# DMX_Eval_Board.net
KiCad netlist of a schematic drawn in EAGLE
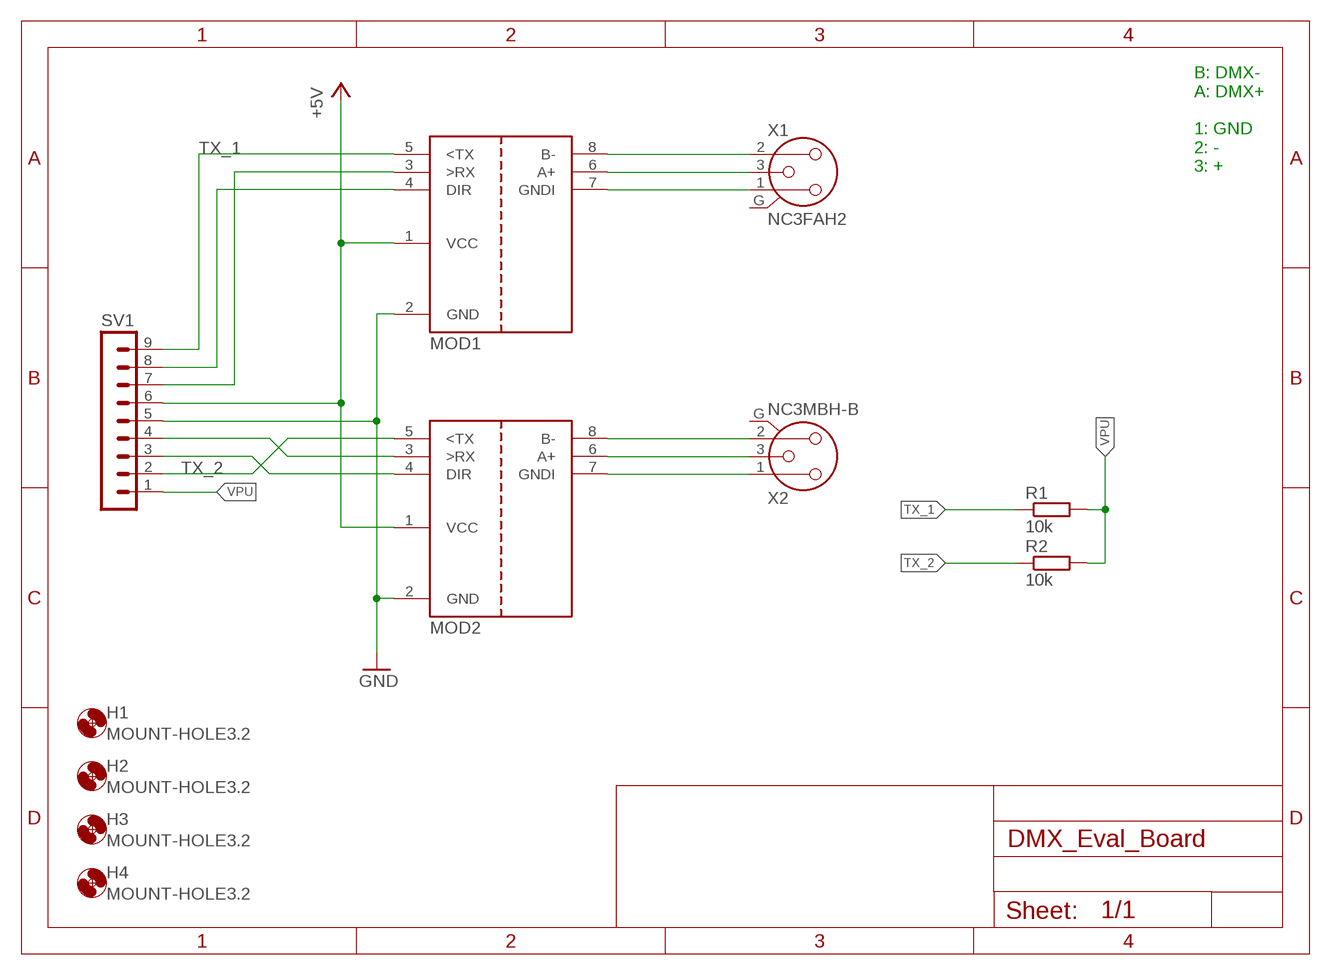
[diagram p0: schematic, sheet 1]

(export (version "E")
  (design (tool "Eeschema 10.0.6"))
  (components
    (comp (ref "H1")
      (value "MOUNT-HOLE3.2")
      (footprint "eagle-import:3,2")
      (libsource (lib "eagle-import") (part "MOUNT-HOLE3.2"))
    )
    (comp (ref "H2")
      (value "MOUNT-HOLE3.2")
      (footprint "eagle-import:3,2")
      (libsource (lib "eagle-import") (part "MOUNT-HOLE3.2"))
    )
    (comp (ref "H3")
      (value "MOUNT-HOLE3.2")
      (footprint "eagle-import:3,2")
      (libsource (lib "eagle-import") (part "MOUNT-HOLE3.2"))
    )
    (comp (ref "H4")
      (value "MOUNT-HOLE3.2")
      (footprint "eagle-import:3,2")
      (libsource (lib "eagle-import") (part "MOUNT-HOLE3.2"))
    )
    (comp (ref "MOD1")
      (value "ISOL_DMX_TRANSCEIVER")
      (footprint "eagle-import:MODULE_DMX_ISO")
      (libsource (lib "eagle-import") (part "ISOL_DMX_TRANSCEIVER"))
    )
    (comp (ref "MOD2")
      (value "ISOL_DMX_TRANSCEIVER")
      (footprint "eagle-import:MODULE_DMX_ISO")
      (libsource (lib "eagle-import") (part "ISOL_DMX_TRANSCEIVER"))
    )
    (comp (ref "R1")
      (value "10k")
      (footprint "eagle-import:R0603")
      (libsource (lib "eagle-import") (part "R-EU_R0603"))
    )
    (comp (ref "R2")
      (value "10k")
      (footprint "eagle-import:R0603")
      (libsource (lib "eagle-import") (part "R-EU_R0603"))
    )
    (comp (ref "SV1")
      (value "MA09-1")
      (footprint "eagle-import:MA09-1")
      (libsource (lib "eagle-import") (part "MA09-1"))
    )
    (comp (ref "X1")
      (value "NC3FAH2")
      (footprint "eagle-import:NC3FAH2")
      (libsource (lib "eagle-import") (part "NC3FAH2"))
    )
    (comp (ref "X2")
      (value "NC3MBH-B")
      (footprint "eagle-import:NC3MBH-B")
      (libsource (lib "eagle-import") (part "NC3MBH-B"))
    )
  )
  (nets
    (net (code "1") (name "+5V") (class "Default")
      (node (ref "MOD1") (pin "1") (pinfunction "VCC_1") (pintype "bidirectional"))
      (node (ref "MOD2") (pin "1") (pinfunction "VCC_1") (pintype "bidirectional"))
      (node (ref "SV1") (pin "6") (pinfunction "6_6") (pintype "passive"))
    )
    (net (code "2") (name "GND") (class "Default")
      (node (ref "MOD1") (pin "2") (pinfunction "GND_2") (pintype "bidirectional"))
      (node (ref "MOD2") (pin "2") (pinfunction "GND_2") (pintype "bidirectional"))
      (node (ref "SV1") (pin "5") (pinfunction "5_5") (pintype "passive"))
    )
    (net (code "3") (name "Net-(MOD1->RX)") (class "Default")
      (node (ref "MOD1") (pin "3") (pinfunction ">RX_3") (pintype "bidirectional"))
      (node (ref "SV1") (pin "7") (pinfunction "7_7") (pintype "passive"))
    )
    (net (code "4") (name "Net-(MOD1-A+)") (class "Default")
      (node (ref "MOD1") (pin "6") (pinfunction "A+_6") (pintype "bidirectional"))
      (node (ref "X1") (pin "3") (pinfunction "3_3") (pintype "passive"))
    )
    (net (code "5") (name "Net-(MOD1-B-)") (class "Default")
      (node (ref "MOD1") (pin "8") (pinfunction "B-_8") (pintype "bidirectional"))
      (node (ref "X1") (pin "2") (pinfunction "1_2") (pintype "passive"))
    )
    (net (code "6") (name "Net-(MOD1-DIR)") (class "Default")
      (node (ref "MOD1") (pin "4") (pinfunction "DIR_4") (pintype "bidirectional"))
      (node (ref "SV1") (pin "8") (pinfunction "8_8") (pintype "passive"))
    )
    (net (code "7") (name "Net-(MOD1-GNDI)") (class "Default")
      (node (ref "MOD1") (pin "7") (pinfunction "GNDI_7") (pintype "bidirectional"))
      (node (ref "X1") (pin "1") (pinfunction "2_1") (pintype "passive"))
    )
    (net (code "8") (name "Net-(MOD2->RX)") (class "Default")
      (node (ref "MOD2") (pin "3") (pinfunction ">RX_3") (pintype "bidirectional"))
      (node (ref "SV1") (pin "4") (pinfunction "4_4") (pintype "passive"))
    )
    (net (code "9") (name "Net-(MOD2-A+)") (class "Default")
      (node (ref "MOD2") (pin "6") (pinfunction "A+_6") (pintype "bidirectional"))
      (node (ref "X2") (pin "3") (pinfunction "3_3") (pintype "passive"))
    )
    (net (code "10") (name "Net-(MOD2-B-)") (class "Default")
      (node (ref "MOD2") (pin "8") (pinfunction "B-_8") (pintype "bidirectional"))
      (node (ref "X2") (pin "2") (pinfunction "2_2") (pintype "passive"))
    )
    (net (code "11") (name "Net-(MOD2-DIR)") (class "Default")
      (node (ref "MOD2") (pin "4") (pinfunction "DIR_4") (pintype "bidirectional"))
      (node (ref "SV1") (pin "3") (pinfunction "3_3") (pintype "passive"))
    )
    (net (code "12") (name "Net-(MOD2-GNDI)") (class "Default")
      (node (ref "MOD2") (pin "7") (pinfunction "GNDI_7") (pintype "bidirectional"))
      (node (ref "X2") (pin "1") (pinfunction "1_1") (pintype "passive"))
    )
    (net (code "13") (name "TX_1") (class "Default")
      (node (ref "MOD1") (pin "5") (pinfunction "<TX_5") (pintype "bidirectional"))
      (node (ref "R1") (pin "1") (pinfunction "1_1") (pintype "passive"))
      (node (ref "SV1") (pin "9") (pinfunction "9_9") (pintype "passive"))
    )
    (net (code "14") (name "TX_2") (class "Default")
      (node (ref "MOD2") (pin "5") (pinfunction "<TX_5") (pintype "bidirectional"))
      (node (ref "R2") (pin "1") (pinfunction "1_1") (pintype "passive"))
      (node (ref "SV1") (pin "2") (pinfunction "2_2") (pintype "passive"))
    )
    (net (code "15") (name "VPU") (class "Default")
      (node (ref "R1") (pin "2") (pinfunction "2_2") (pintype "passive"))
      (node (ref "R2") (pin "2") (pinfunction "2_2") (pintype "passive"))
      (node (ref "SV1") (pin "1") (pinfunction "1_1") (pintype "passive"))
    )
    (net (code "16") (name "unconnected-(X1-PadG)") (class "Default")
      (node (ref "X1") (pin "G") (pinfunction "G_G") (pintype "passive"))
    )
    (net (code "17") (name "unconnected-(X2-PadG)") (class "Default")
      (node (ref "X2") (pin "G") (pinfunction "G_G") (pintype "passive"))
    )
  )
)
